# Power.net
KiCad netlist of a schematic drawn in Altium Designer
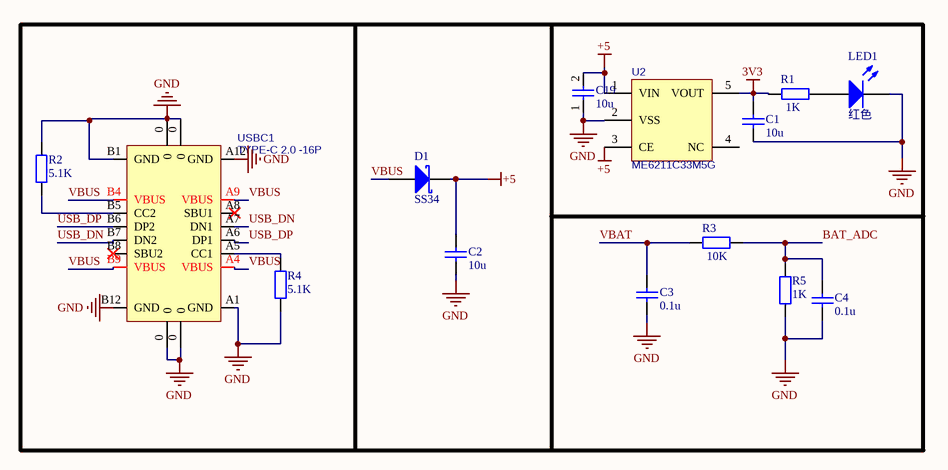
[diagram p0: Power.SchDoc]

(export (version "E")
  (design (tool "Eeschema 10.0.6"))
  (components
    (comp (ref "C1")
      (value "10u")
      (footprint "C0402_M")
      (description "贴片电容/MLCC电容")
      (libsource (lib "0.1 - 电阻-电容-电感-保险丝-晶振-晶体-磁珠-电位器-法拉电容-馈通电容") (part "C"))
    )
    (comp (ref "C2")
      (value "10u")
      (footprint "C0402_M")
      (description "贴片电容/MLCC电容")
      (libsource (lib "0.1 - 电阻-电容-电感-保险丝-晶振-晶体-磁珠-电位器-法拉电容-馈通电容") (part "C"))
    )
    (comp (ref "C3")
      (value "0.1u")
      (footprint "C0402_M")
      (description "贴片电容/MLCC电容")
      (libsource (lib "0.1 - 电阻-电容-电感-保险丝-晶振-晶体-磁珠-电位器-法拉电容-馈通电容") (part "C"))
    )
    (comp (ref "C4")
      (value "0.1u")
      (footprint "C0402_M")
      (description "贴片电容/MLCC电容")
      (libsource (lib "0.1 - 电阻-电容-电感-保险丝-晶振-晶体-磁珠-电位器-法拉电容-馈通电容") (part "C"))
    )
    (comp (ref "C19")
      (value "10u")
      (footprint "C0402_M")
      (description "贴片电容/MLCC电容")
      (libsource (lib "") (part "C_1"))
    )
    (comp (ref "D1")
      (value "SS34")
      (footprint "SOD-123")
      (description "肖特基二极管")
      (libsource (lib "0.2 - 二极管-TVS-ESD-整流桥-放电管") (part "SS34"))
    )
    (comp (ref "LED1")
      (value "红色")
      (footprint "LED0603_R")
      (description "贴片LED")
      (libsource (lib "0.3 - LED发光二极管-IR二极管_接收管-光耦") (part "LED"))
    )
    (comp (ref "R1")
      (value "1K")
      (footprint "R0402_M")
      (description "贴片电阻")
      (libsource (lib "0.1 - 电阻-电容-电感-保险丝-晶振-晶体-磁珠-电位器-法拉电容-馈通电容") (part "R"))
    )
    (comp (ref "R2")
      (value "5.1K")
      (footprint "R0402_M")
      (description "贴片电阻")
      (libsource (lib "0.1 - 电阻-电容-电感-保险丝-晶振-晶体-磁珠-电位器-法拉电容-馈通电容") (part "R"))
    )
    (comp (ref "R3")
      (value "10K")
      (footprint "R0402_M")
      (description "贴片电阻")
      (libsource (lib "0.1 - 电阻-电容-电感-保险丝-晶振-晶体-磁珠-电位器-法拉电容-馈通电容") (part "R"))
    )
    (comp (ref "R4")
      (value "5.1K")
      (footprint "R0402_M")
      (description "贴片电阻")
      (libsource (lib "0.1 - 电阻-电容-电感-保险丝-晶振-晶体-磁珠-电位器-法拉电容-馈通电容") (part "R"))
    )
    (comp (ref "R5")
      (value "1K")
      (footprint "R0402_M")
      (description "贴片电阻")
      (libsource (lib "0.1 - 电阻-电容-电感-保险丝-晶振-晶体-磁珠-电位器-法拉电容-馈通电容") (part "R"))
    )
    (comp (ref "U2")
      (value "ME6211C33M5G")
      (footprint "SOT-23-5")
      (description "LDO 3.3V/0.5A")
      (libsource (lib "0.7 - 电源类芯片") (part "ME6211C33"))
    )
    (comp (ref "USBC1")
      (value "TYPE-C 2.0 -16P")
      (footprint "USB-C-SMD_16P")
      (description "USB2.0_Type-C_16Pin母座")
      (libsource (lib "0.6 - 电源_音频_USB Type-C_HDMI_XT60_5557_D-SUB_RJ45_SD-TF_SIM插座") (part "USB2.0_Type-C_16Pin"))
    )
  )
  (nets
    (net (code "1") (name "+5") (class "Default")
      (node (ref "C19") (pin "2") (pinfunction "2_2") (pintype "passive"))
      (node (ref "C2") (pin "2") (pinfunction "2_2") (pintype "passive"))
      (node (ref "D1") (pin "2") (pinfunction "K_2") (pintype "passive"))
      (node (ref "U2") (pin "1") (pinfunction "VIN_1") (pintype "passive"))
      (node (ref "U2") (pin "3") (pinfunction "CE_3") (pintype "passive"))
    )
    (net (code "2") (name "/BAT_ADC") (class "Default")
      (node (ref "C4") (pin "1") (pinfunction "1_1") (pintype "passive"))
      (node (ref "R3") (pin "2") (pinfunction "2_2") (pintype "passive"))
      (node (ref "R5") (pin "2") (pinfunction "2_2") (pintype "passive"))
    )
    (net (code "3") (name "/USB_DN") (class "Default")
      (node (ref "USBC1") (pin "A7") (pinfunction "DN1_A7") (pintype "passive"))
      (node (ref "USBC1") (pin "B7") (pinfunction "DN2_B7") (pintype "passive"))
    )
    (net (code "4") (name "/USB_DP") (class "Default")
      (node (ref "USBC1") (pin "A6") (pinfunction "DP1_A6") (pintype "passive"))
      (node (ref "USBC1") (pin "B6") (pinfunction "DP2_B6") (pintype "passive"))
    )
    (net (code "5") (name "/VBAT") (class "Default")
      (node (ref "C3") (pin "2") (pinfunction "2_2") (pintype "passive"))
      (node (ref "R3") (pin "1") (pinfunction "1_1") (pintype "passive"))
    )
    (net (code "6") (name "/VBUS") (class "Default")
      (node (ref "D1") (pin "1") (pinfunction "A_1") (pintype "passive"))
      (node (ref "USBC1") (pin "A4") (pinfunction "VBUS_A4") (pintype "passive"))
      (node (ref "USBC1") (pin "A9") (pinfunction "VBUS_A9") (pintype "passive"))
      (node (ref "USBC1") (pin "B4") (pinfunction "VBUS_B4") (pintype "passive"))
      (node (ref "USBC1") (pin "B9") (pinfunction "VBUS_B9") (pintype "passive"))
    )
    (net (code "7") (name "3V3") (class "Default")
      (node (ref "C1") (pin "2") (pinfunction "2_2") (pintype "passive"))
      (node (ref "R1") (pin "1") (pinfunction "1_1") (pintype "passive"))
      (node (ref "U2") (pin "5") (pinfunction "VOUT_5") (pintype "passive"))
    )
    (net (code "8") (name "GND") (class "Default")
      (node (ref "C1") (pin "1") (pinfunction "1_1") (pintype "passive"))
      (node (ref "C19") (pin "1") (pinfunction "1_1") (pintype "passive"))
      (node (ref "C2") (pin "1") (pinfunction "1_1") (pintype "passive"))
      (node (ref "C3") (pin "1") (pinfunction "1_1") (pintype "passive"))
      (node (ref "C4") (pin "2") (pinfunction "2_2") (pintype "passive"))
      (node (ref "LED1") (pin "2") (pinfunction "K_2") (pintype "passive"))
      (node (ref "R2") (pin "2") (pinfunction "2_2") (pintype "passive"))
      (node (ref "R4") (pin "1") (pinfunction "1_1") (pintype "passive"))
      (node (ref "R5") (pin "1") (pinfunction "1_1") (pintype "passive"))
      (node (ref "U2") (pin "2") (pinfunction "VSS_2") (pintype "passive"))
      (node (ref "USBC1") (pin "0") (pinfunction "0_0") (pintype "passive"))
      (node (ref "USBC1") (pin "A1") (pinfunction "GND_A1") (pintype "passive"))
      (node (ref "USBC1") (pin "A12") (pinfunction "GND_A12") (pintype "passive"))
      (node (ref "USBC1") (pin "B1") (pinfunction "GND_B1") (pintype "passive"))
      (node (ref "USBC1") (pin "B12") (pinfunction "GND_B12") (pintype "passive"))
    )
    (net (code "9") (name "Net-(LED1-A)") (class "Default")
      (node (ref "LED1") (pin "1") (pinfunction "A_1") (pintype "passive"))
      (node (ref "R1") (pin "2") (pinfunction "2_2") (pintype "passive"))
    )
    (net (code "10") (name "Net-(USBC1-CC1)") (class "Default")
      (node (ref "R4") (pin "2") (pinfunction "2_2") (pintype "passive"))
      (node (ref "USBC1") (pin "A5") (pinfunction "CC1_A5") (pintype "passive"))
    )
    (net (code "11") (name "Net-(USBC1-CC2)") (class "Default")
      (node (ref "R2") (pin "1") (pinfunction "1_1") (pintype "passive"))
      (node (ref "USBC1") (pin "B5") (pinfunction "CC2_B5") (pintype "passive"))
    )
    (net (code "12") (name "unconnected-(U2-NC-Pad4)") (class "Default")
      (node (ref "U2") (pin "4") (pinfunction "NC_4") (pintype "passive"))
    )
    (net (code "13") (name "unconnected-(USBC1-SBU1-PadA8)") (class "Default")
      (node (ref "USBC1") (pin "A8") (pinfunction "SBU1_A8") (pintype "passive+no_connect"))
    )
    (net (code "14") (name "unconnected-(USBC1-SBU2-PadB8)") (class "Default")
      (node (ref "USBC1") (pin "B8") (pinfunction "SBU2_B8") (pintype "passive+no_connect"))
    )
  )
)
